# riffle-sqA.net
KiCad netlist of a schematic drawn in EAGLE
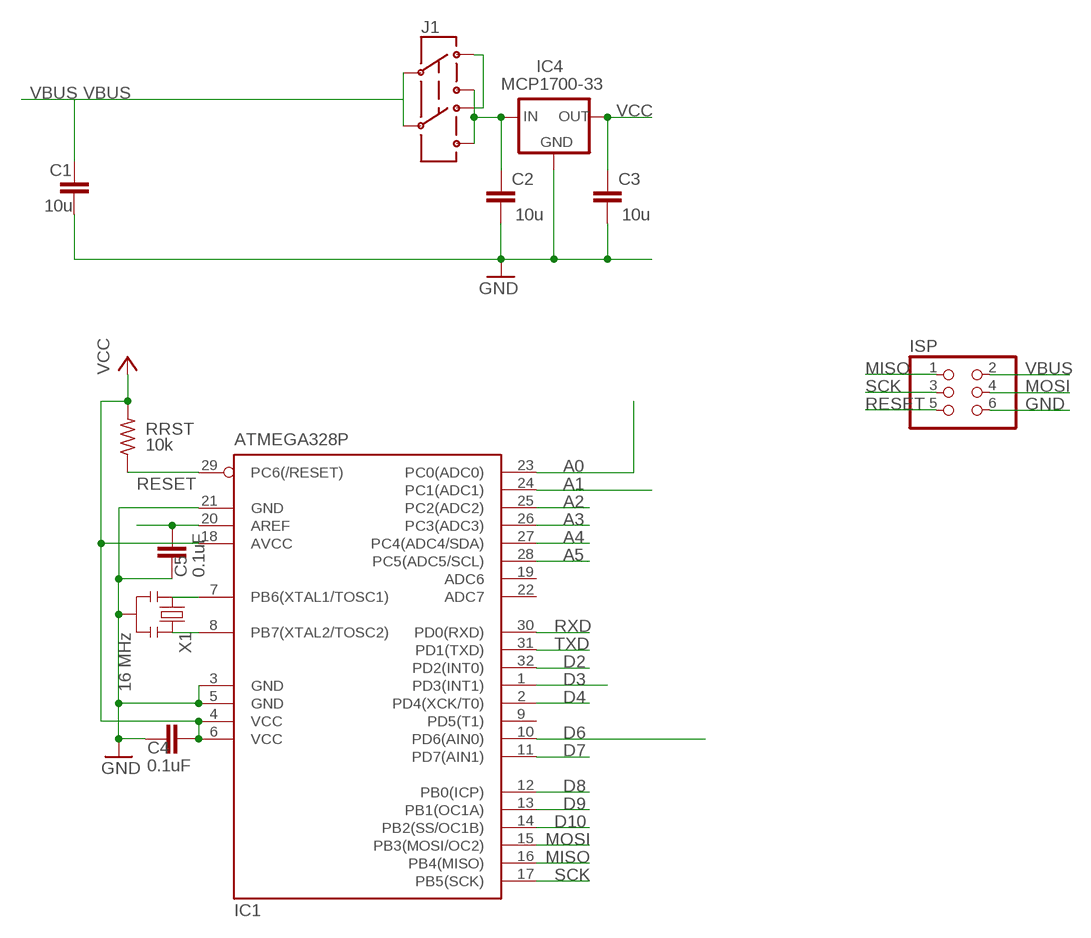
[diagram p0: schematic, sheet 1]

(export (version "E")
  (design (tool "Eeschema 10.0.6"))
  (components
    (comp (ref "C1")
      (value "10u")
      (footprint "eagle-import:C0805")
      (libsource (lib "eagle-import") (part "resistor_C-EUC0805"))
    )
    (comp (ref "C2")
      (value "10u")
      (footprint "eagle-import:C0805")
      (libsource (lib "eagle-import") (part "resistor_C-EUC0805"))
    )
    (comp (ref "C3")
      (value "10u")
      (footprint "eagle-import:C0805")
      (libsource (lib "eagle-import") (part "resistor_C-EUC0805"))
    )
    (comp (ref "C4")
      (value "0.1uF")
      (footprint "eagle-import:C0805")
      (libsource (lib "eagle-import") (part "C-EUC0805"))
    )
    (comp (ref "C5")
      (value "0.1uF")
      (footprint "eagle-import:C0805")
      (libsource (lib "eagle-import") (part "C-EUC0805"))
    )
    (comp (ref "IC1")
      (value "ATMEGA328P")
      (footprint "eagle-import:TQFP32-08")
      (fields (field (name "MPN") "ATMEGA8-16AU"))
      (libsource (lib "eagle-import") (part "MEGA8-AI"))
    )
    (comp (ref "IC4")
      (value "MCP1700-33")
      (footprint "eagle-import:SOT23")
      (libsource (lib "eagle-import") (part "MCP1700SOT233"))
    )
    (comp (ref "ISP")
      (value "PINHD-2X3")
      (footprint "eagle-import:2X03")
      (libsource (lib "eagle-import") (part "PINHD-2X3"))
    )
    (comp (ref "J1")
      (value "AYZ0202")
      (footprint "eagle-import:AYZ0202")
      (libsource (lib "eagle-import") (part "AYZ0202"))
    )
    (comp (ref "RRST")
      (value "10k")
      (footprint "eagle-import:R0805@1")
      (libsource (lib "eagle-import") (part "R-US_R0805"))
    )
    (comp (ref "X1")
      (value "16 MHz")
      (footprint "eagle-import:RESONATOR-SMD")
      (libsource (lib "eagle-import") (part "RESONATORSMD"))
    )
  )
  (nets
    (net (code "1") (name "/A0") (class "Default")
      (node (ref "IC1") (pin "23") (pinfunction "PC0(ADC0)_23") (pintype "bidirectional"))
    )
    (net (code "2") (name "/A1") (class "Default")
      (node (ref "IC1") (pin "24") (pinfunction "PC1(ADC1)_24") (pintype "bidirectional"))
    )
    (net (code "3") (name "/A2") (class "Default")
      (node (ref "IC1") (pin "25") (pinfunction "PC2(ADC2)_25") (pintype "bidirectional"))
    )
    (net (code "4") (name "/A3") (class "Default")
      (node (ref "IC1") (pin "26") (pinfunction "PC3(ADC3)_26") (pintype "bidirectional"))
    )
    (net (code "5") (name "/A4") (class "Default")
      (node (ref "IC1") (pin "27") (pinfunction "PC4(ADC4/SDA)_27") (pintype "bidirectional"))
    )
    (net (code "6") (name "/A5") (class "Default")
      (node (ref "IC1") (pin "28") (pinfunction "PC5(ADC5/SCL)_28") (pintype "bidirectional"))
    )
    (net (code "7") (name "/D2") (class "Default")
      (node (ref "IC1") (pin "32") (pinfunction "PD2(INT0)_32") (pintype "bidirectional"))
    )
    (net (code "8") (name "/D3") (class "Default")
      (node (ref "IC1") (pin "1") (pinfunction "PD3(INT1)_1") (pintype "bidirectional"))
    )
    (net (code "9") (name "/D4") (class "Default")
      (node (ref "IC1") (pin "2") (pinfunction "PD4(XCK/T0)_2") (pintype "bidirectional"))
    )
    (net (code "10") (name "/D6") (class "Default")
      (node (ref "IC1") (pin "10") (pinfunction "PD6(AIN0)_10") (pintype "bidirectional"))
    )
    (net (code "11") (name "/D7") (class "Default")
      (node (ref "IC1") (pin "11") (pinfunction "PD7(AIN1)_11") (pintype "bidirectional"))
    )
    (net (code "12") (name "/D8") (class "Default")
      (node (ref "IC1") (pin "12") (pinfunction "PB0(ICP)_12") (pintype "bidirectional"))
    )
    (net (code "13") (name "/D9") (class "Default")
      (node (ref "IC1") (pin "13") (pinfunction "PB1(OC1A)_13") (pintype "bidirectional"))
    )
    (net (code "14") (name "/D10") (class "Default")
      (node (ref "IC1") (pin "14") (pinfunction "PB2(SS/OC1B)_14") (pintype "bidirectional"))
    )
    (net (code "15") (name "/MISO") (class "Default")
      (node (ref "IC1") (pin "16") (pinfunction "PB4(MISO)_16") (pintype "bidirectional"))
      (node (ref "ISP") (pin "1") (pinfunction "1_1") (pintype "passive"))
    )
    (net (code "16") (name "/MOSI") (class "Default")
      (node (ref "IC1") (pin "15") (pinfunction "PB3(MOSI/OC2)_15") (pintype "bidirectional"))
      (node (ref "ISP") (pin "4") (pinfunction "4_4") (pintype "passive"))
    )
    (net (code "17") (name "/RESET") (class "Default")
      (node (ref "IC1") (pin "29") (pinfunction "PC6(/RESET)_29") (pintype "bidirectional"))
      (node (ref "ISP") (pin "5") (pinfunction "5_5") (pintype "passive"))
      (node (ref "RRST") (pin "1") (pinfunction "1_1") (pintype "passive"))
    )
    (net (code "18") (name "/RXD") (class "Default")
      (node (ref "IC1") (pin "30") (pinfunction "PD0(RXD)_30") (pintype "bidirectional"))
    )
    (net (code "19") (name "/SCK") (class "Default")
      (node (ref "IC1") (pin "17") (pinfunction "PB5(SCK)_17") (pintype "bidirectional"))
      (node (ref "ISP") (pin "3") (pinfunction "3_3") (pintype "passive"))
    )
    (net (code "20") (name "/TXD") (class "Default")
      (node (ref "IC1") (pin "31") (pinfunction "PD1(TXD)_31") (pintype "bidirectional"))
    )
    (net (code "21") (name "/VBUS") (class "Default")
      (node (ref "C1") (pin "1") (pinfunction "1_1") (pintype "passive"))
      (node (ref "ISP") (pin "2") (pinfunction "2_2") (pintype "passive"))
      (node (ref "J1") (pin "2") (pinfunction "2_2") (pintype "bidirectional"))
      (node (ref "J1") (pin "5") (pinfunction "5_5") (pintype "bidirectional"))
    )
    (net (code "22") (name "GND") (class "Default")
      (node (ref "C1") (pin "2") (pinfunction "2_2") (pintype "passive"))
      (node (ref "C2") (pin "2") (pinfunction "2_2") (pintype "passive"))
      (node (ref "C3") (pin "2") (pinfunction "2_2") (pintype "passive"))
      (node (ref "C4") (pin "1") (pinfunction "1_1") (pintype "passive"))
      (node (ref "C5") (pin "1") (pinfunction "1_1") (pintype "passive"))
      (node (ref "IC1") (pin "21") (pinfunction "GND_21") (pintype "power_in"))
      (node (ref "IC1") (pin "3") (pinfunction "GND_3") (pintype "power_in"))
      (node (ref "IC1") (pin "5") (pinfunction "GND_5") (pintype "power_in"))
      (node (ref "IC4") (pin "1") (pinfunction "GND_1") (pintype "input"))
      (node (ref "ISP") (pin "6") (pinfunction "6_6") (pintype "passive"))
      (node (ref "X1") (pin "2") (pinfunction "2_2") (pintype "passive"))
    )
    (net (code "23") (name "Net-(IC1-AREF)") (class "Default")
      (node (ref "C5") (pin "2") (pinfunction "2_2") (pintype "passive"))
      (node (ref "IC1") (pin "20") (pinfunction "AREF_20") (pintype "passive"))
    )
    (net (code "24") (name "Net-(IC1-PB6(XTAL1{slash}TOSC1))") (class "Default")
      (node (ref "IC1") (pin "7") (pinfunction "PB6(XTAL1/TOSC1)_7") (pintype "bidirectional"))
      (node (ref "X1") (pin "1") (pinfunction "1_1") (pintype "passive"))
    )
    (net (code "25") (name "Net-(IC1-PB7(XTAL2{slash}TOSC2))") (class "Default")
      (node (ref "IC1") (pin "8") (pinfunction "PB7(XTAL2/TOSC2)_8") (pintype "bidirectional"))
      (node (ref "X1") (pin "3") (pinfunction "3_3") (pintype "passive"))
    )
    (net (code "26") (name "Net-(IC4-IN)") (class "Default")
      (node (ref "C2") (pin "1") (pinfunction "1_1") (pintype "passive"))
      (node (ref "IC4") (pin "3") (pinfunction "IN_3") (pintype "input"))
      (node (ref "J1") (pin "1") (pinfunction "3_1") (pintype "bidirectional"))
      (node (ref "J1") (pin "4") (pinfunction "6_4") (pintype "bidirectional"))
    )
    (net (code "27") (name "Net-(J1-1)") (class "Default")
      (node (ref "J1") (pin "3") (pinfunction "1_3") (pintype "bidirectional"))
      (node (ref "J1") (pin "6") (pinfunction "4_6") (pintype "bidirectional"))
    )
    (net (code "28") (name "VCC") (class "Default")
      (node (ref "C3") (pin "1") (pinfunction "1_1") (pintype "passive"))
      (node (ref "C4") (pin "2") (pinfunction "2_2") (pintype "passive"))
      (node (ref "IC1") (pin "18") (pinfunction "AVCC_18") (pintype "power_in"))
      (node (ref "IC1") (pin "4") (pinfunction "VCC_4") (pintype "power_in"))
      (node (ref "IC1") (pin "6") (pinfunction "VCC_6") (pintype "power_in"))
      (node (ref "IC4") (pin "2") (pinfunction "OUT_2") (pintype "passive"))
      (node (ref "RRST") (pin "2") (pinfunction "2_2") (pintype "passive"))
    )
    (net (code "29") (name "unconnected-(IC1-ADC6-Pad19)") (class "Default")
      (node (ref "IC1") (pin "19") (pinfunction "ADC6_19") (pintype "bidirectional"))
    )
    (net (code "30") (name "unconnected-(IC1-ADC7-Pad22)") (class "Default")
      (node (ref "IC1") (pin "22") (pinfunction "ADC7_22") (pintype "bidirectional"))
    )
    (net (code "31") (name "unconnected-(IC1-PD5(T1)-Pad9)") (class "Default")
      (node (ref "IC1") (pin "9") (pinfunction "PD5(T1)_9") (pintype "bidirectional"))
    )
  )
)
